# Port_Expander.net
KiCad netlist of a schematic drawn in Altium Designer
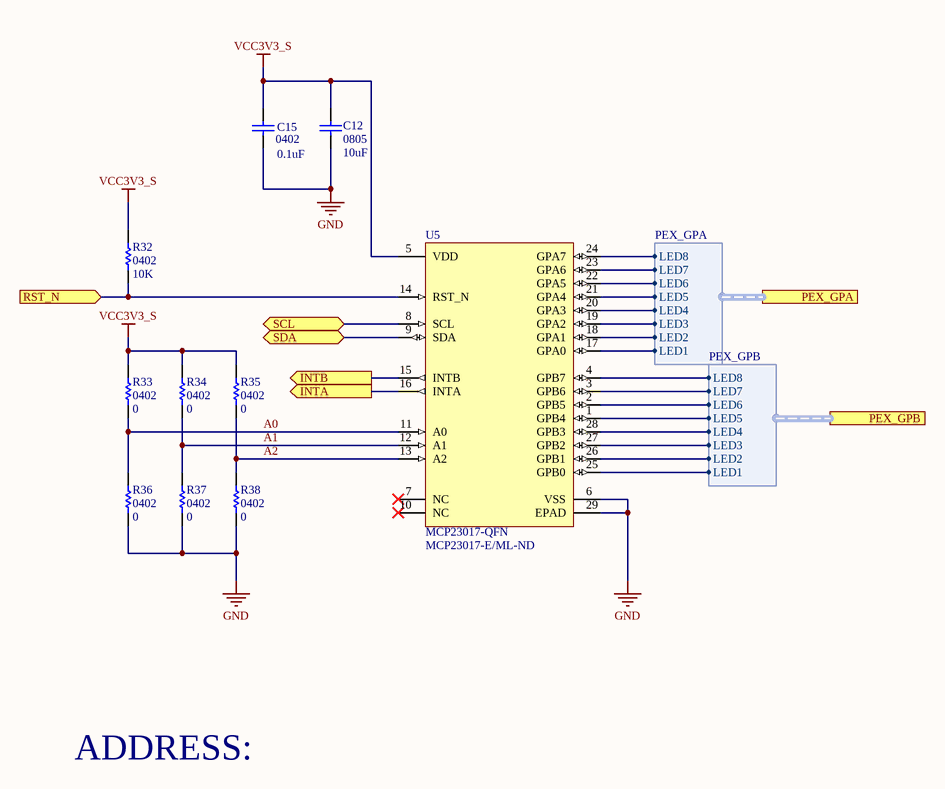
[diagram p0: Port Expander.SchDoc]

(export (version "E")
  (design (tool "Eeschema 10.0.6"))
  (components
    (comp (ref "C12")
      (value "0805")
      (footprint "CAP0805R")
      (description "Capacitor")
      (fields
        (field (name "ALTIUM_VALUE") "10uF")
        (field (name "MANUFACTURER") "TDK")
        (field (name "MANUFACTURER PART NUMBER") "CGA4J1X7R0J106K125AC")
        (field (name "PUBLISHER") "Altium Limited")
      )
      (libsource (lib "Miscellaneous Devices") (part "Cap"))
    )
    (comp (ref "C15")
      (value "0402")
      (footprint "CAP0402R")
      (description "Capacitor (Semiconductor SIM Model)")
      (fields
        (field (name "ALTIUM_VALUE") "0.1uF")
        (field (name "MANUFACTURER") "Murata")
        (field (name "MANUFACTURER PART NUMBER") "GCM155R71C104KA55J")
        (field (name "PUBLISHER") "Altium Limited")
      )
      (libsource (lib "Miscellaneous Devices") (part "Cap Semi"))
    )
    (comp (ref "R32")
      (value "0402")
      (footprint "RES0402R")
      (description "Resistor")
      (fields (field (name "ALTIUM_VALUE") "10K") (field (name "PUBLISHER") "Altium Limited"))
      (libsource (lib "Miscellaneous Devices") (part "Res1"))
    )
    (comp (ref "R33")
      (value "0402")
      (footprint "RES0402R")
      (description "Resistor")
      (fields
        (field (name "ALTIUM_VALUE") "0")
        (field (name "MANUFACTURER") "Panasonic")
        (field (name "MANUFACTURER PART NUMBER") "ERJ2GE0R00X")
        (field (name "PUBLISHER") "Altium Limited")
      )
      (libsource (lib "Miscellaneous Devices") (part "Res1"))
    )
    (comp (ref "R34")
      (value "0402")
      (footprint "RES0402R")
      (description "Resistor")
      (fields
        (field (name "ALTIUM_VALUE") "0")
        (field (name "MANUFACTURER") "Panasonic")
        (field (name "MANUFACTURER PART NUMBER") "ERJ2GE0R00X")
        (field (name "PUBLISHER") "Altium Limited")
      )
      (libsource (lib "Miscellaneous Devices") (part "Res1"))
    )
    (comp (ref "R35")
      (value "0402")
      (footprint "RES0402R")
      (description "Resistor")
      (fields
        (field (name "ALTIUM_VALUE") "0")
        (field (name "MANUFACTURER") "Panasonic")
        (field (name "MANUFACTURER PART NUMBER") "ERJ2GE0R00X")
        (field (name "PUBLISHER") "Altium Limited")
      )
      (libsource (lib "Miscellaneous Devices") (part "Res1"))
    )
    (comp (ref "R36")
      (value "0402")
      (footprint "RES0402R")
      (description "Resistor")
      (fields
        (field (name "ALTIUM_VALUE") "0")
        (field (name "MANUFACTURER") "Panasonic")
        (field (name "MANUFACTURER PART NUMBER") "ERJ2GE0R00X")
        (field (name "PUBLISHER") "Altium Limited")
      )
      (libsource (lib "Miscellaneous Devices") (part "Res1"))
    )
    (comp (ref "R37")
      (value "0402")
      (footprint "RES0402R")
      (description "Resistor")
      (fields
        (field (name "ALTIUM_VALUE") "0")
        (field (name "MANUFACTURER") "Panasonic")
        (field (name "MANUFACTURER PART NUMBER") "ERJ2GE0R00X")
        (field (name "PUBLISHER") "Altium Limited")
      )
      (libsource (lib "Miscellaneous Devices") (part "Res1"))
    )
    (comp (ref "R38")
      (value "0402")
      (footprint "RES0402R")
      (description "Resistor")
      (fields
        (field (name "ALTIUM_VALUE") "0")
        (field (name "MANUFACTURER") "Panasonic")
        (field (name "MANUFACTURER PART NUMBER") "ERJ2GE0R00X")
        (field (name "PUBLISHER") "Altium Limited")
      )
      (libsource (lib "Miscellaneous Devices") (part "Res1"))
    )
    (comp (ref "U5")
      (value "MCP23017-QFN")
      (footprint "QFN65P600X600X100-29")
      (fields (field (name "SUPPLIER PART NUMBER 1") "MCP23017-E/ML-ND"))
      (libsource (lib "heron-general") (part "MCP23017-QFN"))
    )
  )
  (nets
    (net (code "3") (name "/A0") (class "Default")
      (node (ref "R33") (pin "1") (pinfunction "1_1") (pintype "passive"))
      (node (ref "R36") (pin "2") (pinfunction "2_2") (pintype "passive"))
      (node (ref "U5") (pin "11") (pinfunction "A0_11") (pintype "input"))
    )
    (net (code "4") (name "/A1") (class "Default")
      (node (ref "R34") (pin "1") (pinfunction "1_1") (pintype "passive"))
      (node (ref "R37") (pin "2") (pinfunction "2_2") (pintype "passive"))
      (node (ref "U5") (pin "12") (pinfunction "A1_12") (pintype "input"))
    )
    (net (code "5") (name "/A2") (class "Default")
      (node (ref "R35") (pin "1") (pinfunction "1_1") (pintype "passive"))
      (node (ref "R38") (pin "2") (pinfunction "2_2") (pintype "passive"))
      (node (ref "U5") (pin "13") (pinfunction "A2_13") (pintype "input"))
    )
    (net (code "6") (name "/INTA") (class "Default")
      (node (ref "U5") (pin "16") (pinfunction "INTA_16") (pintype "output"))
    )
    (net (code "7") (name "/INTB") (class "Default")
      (node (ref "U5") (pin "15") (pinfunction "INTB_15") (pintype "output"))
    )
    (net (code "9") (name "/RST_N") (class "Default")
      (node (ref "R32") (pin "1") (pinfunction "1_1") (pintype "passive"))
      (node (ref "U5") (pin "14") (pinfunction "RST_N_14") (pintype "input"))
    )
    (net (code "10") (name "/SCL") (class "Default")
      (node (ref "U5") (pin "8") (pinfunction "SCL_8") (pintype "input"))
    )
    (net (code "11") (name "/SDA") (class "Default")
      (node (ref "U5") (pin "9") (pinfunction "SDA_9") (pintype "bidirectional"))
    )
    (net (code "13") (name "GND") (class "Default")
      (node (ref "C12") (pin "1") (pinfunction "1_1") (pintype "passive"))
      (node (ref "C15") (pin "1") (pinfunction "1_1") (pintype "passive"))
      (node (ref "R36") (pin "1") (pinfunction "1_1") (pintype "passive"))
      (node (ref "R37") (pin "1") (pinfunction "1_1") (pintype "passive"))
      (node (ref "R38") (pin "1") (pinfunction "1_1") (pintype "passive"))
      (node (ref "U5") (pin "29") (pinfunction "EPAD_29") (pintype "power_in"))
      (node (ref "U5") (pin "6") (pinfunction "VSS_6") (pintype "power_in"))
    )
    (net (code "14") (name "VCC3V3_S") (class "Default")
      (node (ref "C12") (pin "2") (pinfunction "2_2") (pintype "passive"))
      (node (ref "C15") (pin "2") (pinfunction "2_2") (pintype "passive"))
      (node (ref "R32") (pin "2") (pinfunction "2_2") (pintype "passive"))
      (node (ref "R33") (pin "2") (pinfunction "2_2") (pintype "passive"))
      (node (ref "R34") (pin "2") (pinfunction "2_2") (pintype "passive"))
      (node (ref "R35") (pin "2") (pinfunction "2_2") (pintype "passive"))
      (node (ref "U5") (pin "5") (pinfunction "VDD_5") (pintype "power_in"))
    )
    (net (code "15") (name "unconnected-(U5-GPA0-Pad17)") (class "Default")
      (node (ref "U5") (pin "17") (pinfunction "GPA0_17") (pintype "bidirectional"))
    )
    (net (code "16") (name "unconnected-(U5-GPA1-Pad18)") (class "Default")
      (node (ref "U5") (pin "18") (pinfunction "GPA1_18") (pintype "bidirectional"))
    )
    (net (code "17") (name "unconnected-(U5-GPA2-Pad19)") (class "Default")
      (node (ref "U5") (pin "19") (pinfunction "GPA2_19") (pintype "bidirectional"))
    )
    (net (code "18") (name "unconnected-(U5-GPA3-Pad20)") (class "Default")
      (node (ref "U5") (pin "20") (pinfunction "GPA3_20") (pintype "bidirectional"))
    )
    (net (code "19") (name "unconnected-(U5-GPA4-Pad21)") (class "Default")
      (node (ref "U5") (pin "21") (pinfunction "GPA4_21") (pintype "bidirectional"))
    )
    (net (code "20") (name "unconnected-(U5-GPA5-Pad22)") (class "Default")
      (node (ref "U5") (pin "22") (pinfunction "GPA5_22") (pintype "bidirectional"))
    )
    (net (code "21") (name "unconnected-(U5-GPA6-Pad23)") (class "Default")
      (node (ref "U5") (pin "23") (pinfunction "GPA6_23") (pintype "bidirectional"))
    )
    (net (code "22") (name "unconnected-(U5-GPA7-Pad24)") (class "Default")
      (node (ref "U5") (pin "24") (pinfunction "GPA7_24") (pintype "bidirectional"))
    )
    (net (code "23") (name "unconnected-(U5-GPB0-Pad25)") (class "Default")
      (node (ref "U5") (pin "25") (pinfunction "GPB0_25") (pintype "bidirectional"))
    )
    (net (code "24") (name "unconnected-(U5-GPB1-Pad26)") (class "Default")
      (node (ref "U5") (pin "26") (pinfunction "GPB1_26") (pintype "bidirectional"))
    )
    (net (code "25") (name "unconnected-(U5-GPB2-Pad27)") (class "Default")
      (node (ref "U5") (pin "27") (pinfunction "GPB2_27") (pintype "bidirectional"))
    )
    (net (code "26") (name "unconnected-(U5-GPB3-Pad28)") (class "Default")
      (node (ref "U5") (pin "28") (pinfunction "GPB3_28") (pintype "bidirectional"))
    )
    (net (code "27") (name "unconnected-(U5-GPB4-Pad1)") (class "Default")
      (node (ref "U5") (pin "1") (pinfunction "GPB4_1") (pintype "bidirectional"))
    )
    (net (code "28") (name "unconnected-(U5-GPB5-Pad2)") (class "Default")
      (node (ref "U5") (pin "2") (pinfunction "GPB5_2") (pintype "bidirectional"))
    )
    (net (code "29") (name "unconnected-(U5-GPB6-Pad3)") (class "Default")
      (node (ref "U5") (pin "3") (pinfunction "GPB6_3") (pintype "bidirectional"))
    )
    (net (code "30") (name "unconnected-(U5-GPB7-Pad4)") (class "Default")
      (node (ref "U5") (pin "4") (pinfunction "GPB7_4") (pintype "bidirectional"))
    )
    (net (code "31") (name "unconnected-(U5-NC-Pad7)") (class "Default")
      (node (ref "U5") (pin "7") (pinfunction "NC_7") (pintype "passive+no_connect"))
    )
    (net (code "32") (name "unconnected-(U5-NC-Pad10)") (class "Default")
      (node (ref "U5") (pin "10") (pinfunction "NC_10") (pintype "passive+no_connect"))
    )
  )
)
